# damp2_v0001.net
KiCad netlist of a schematic drawn in EAGLE
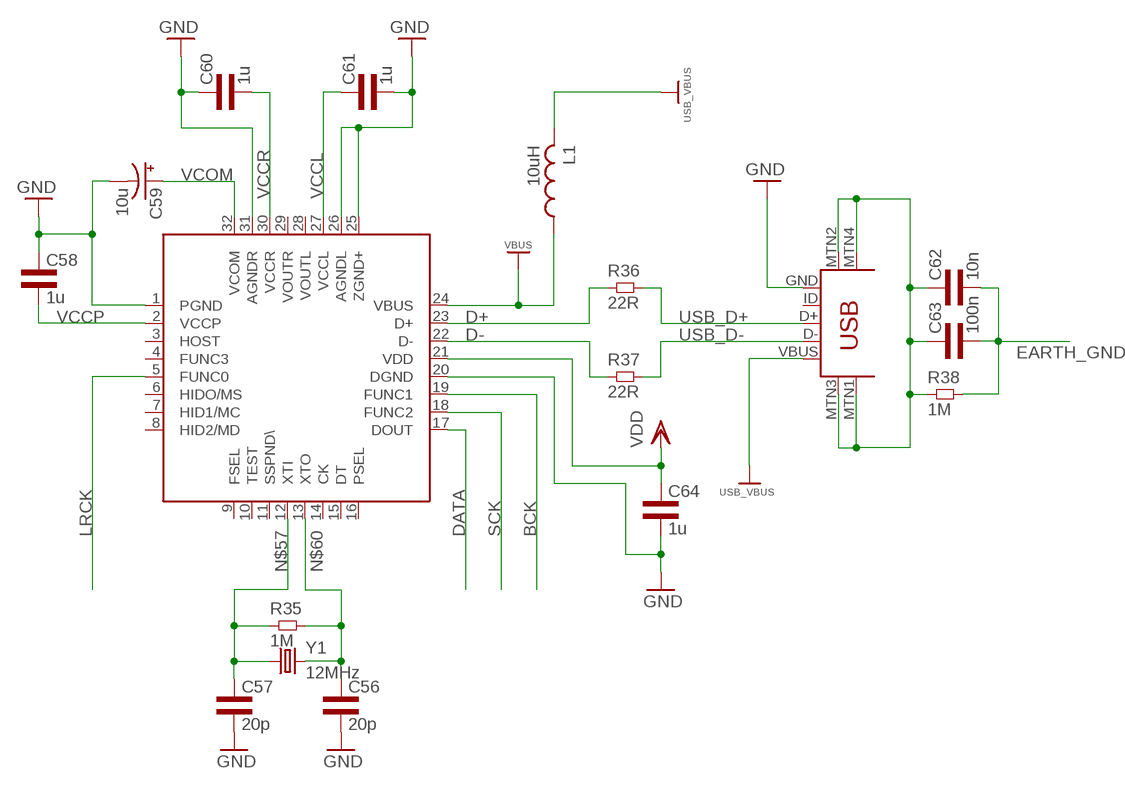
[diagram p0: schematic, sheet 1]
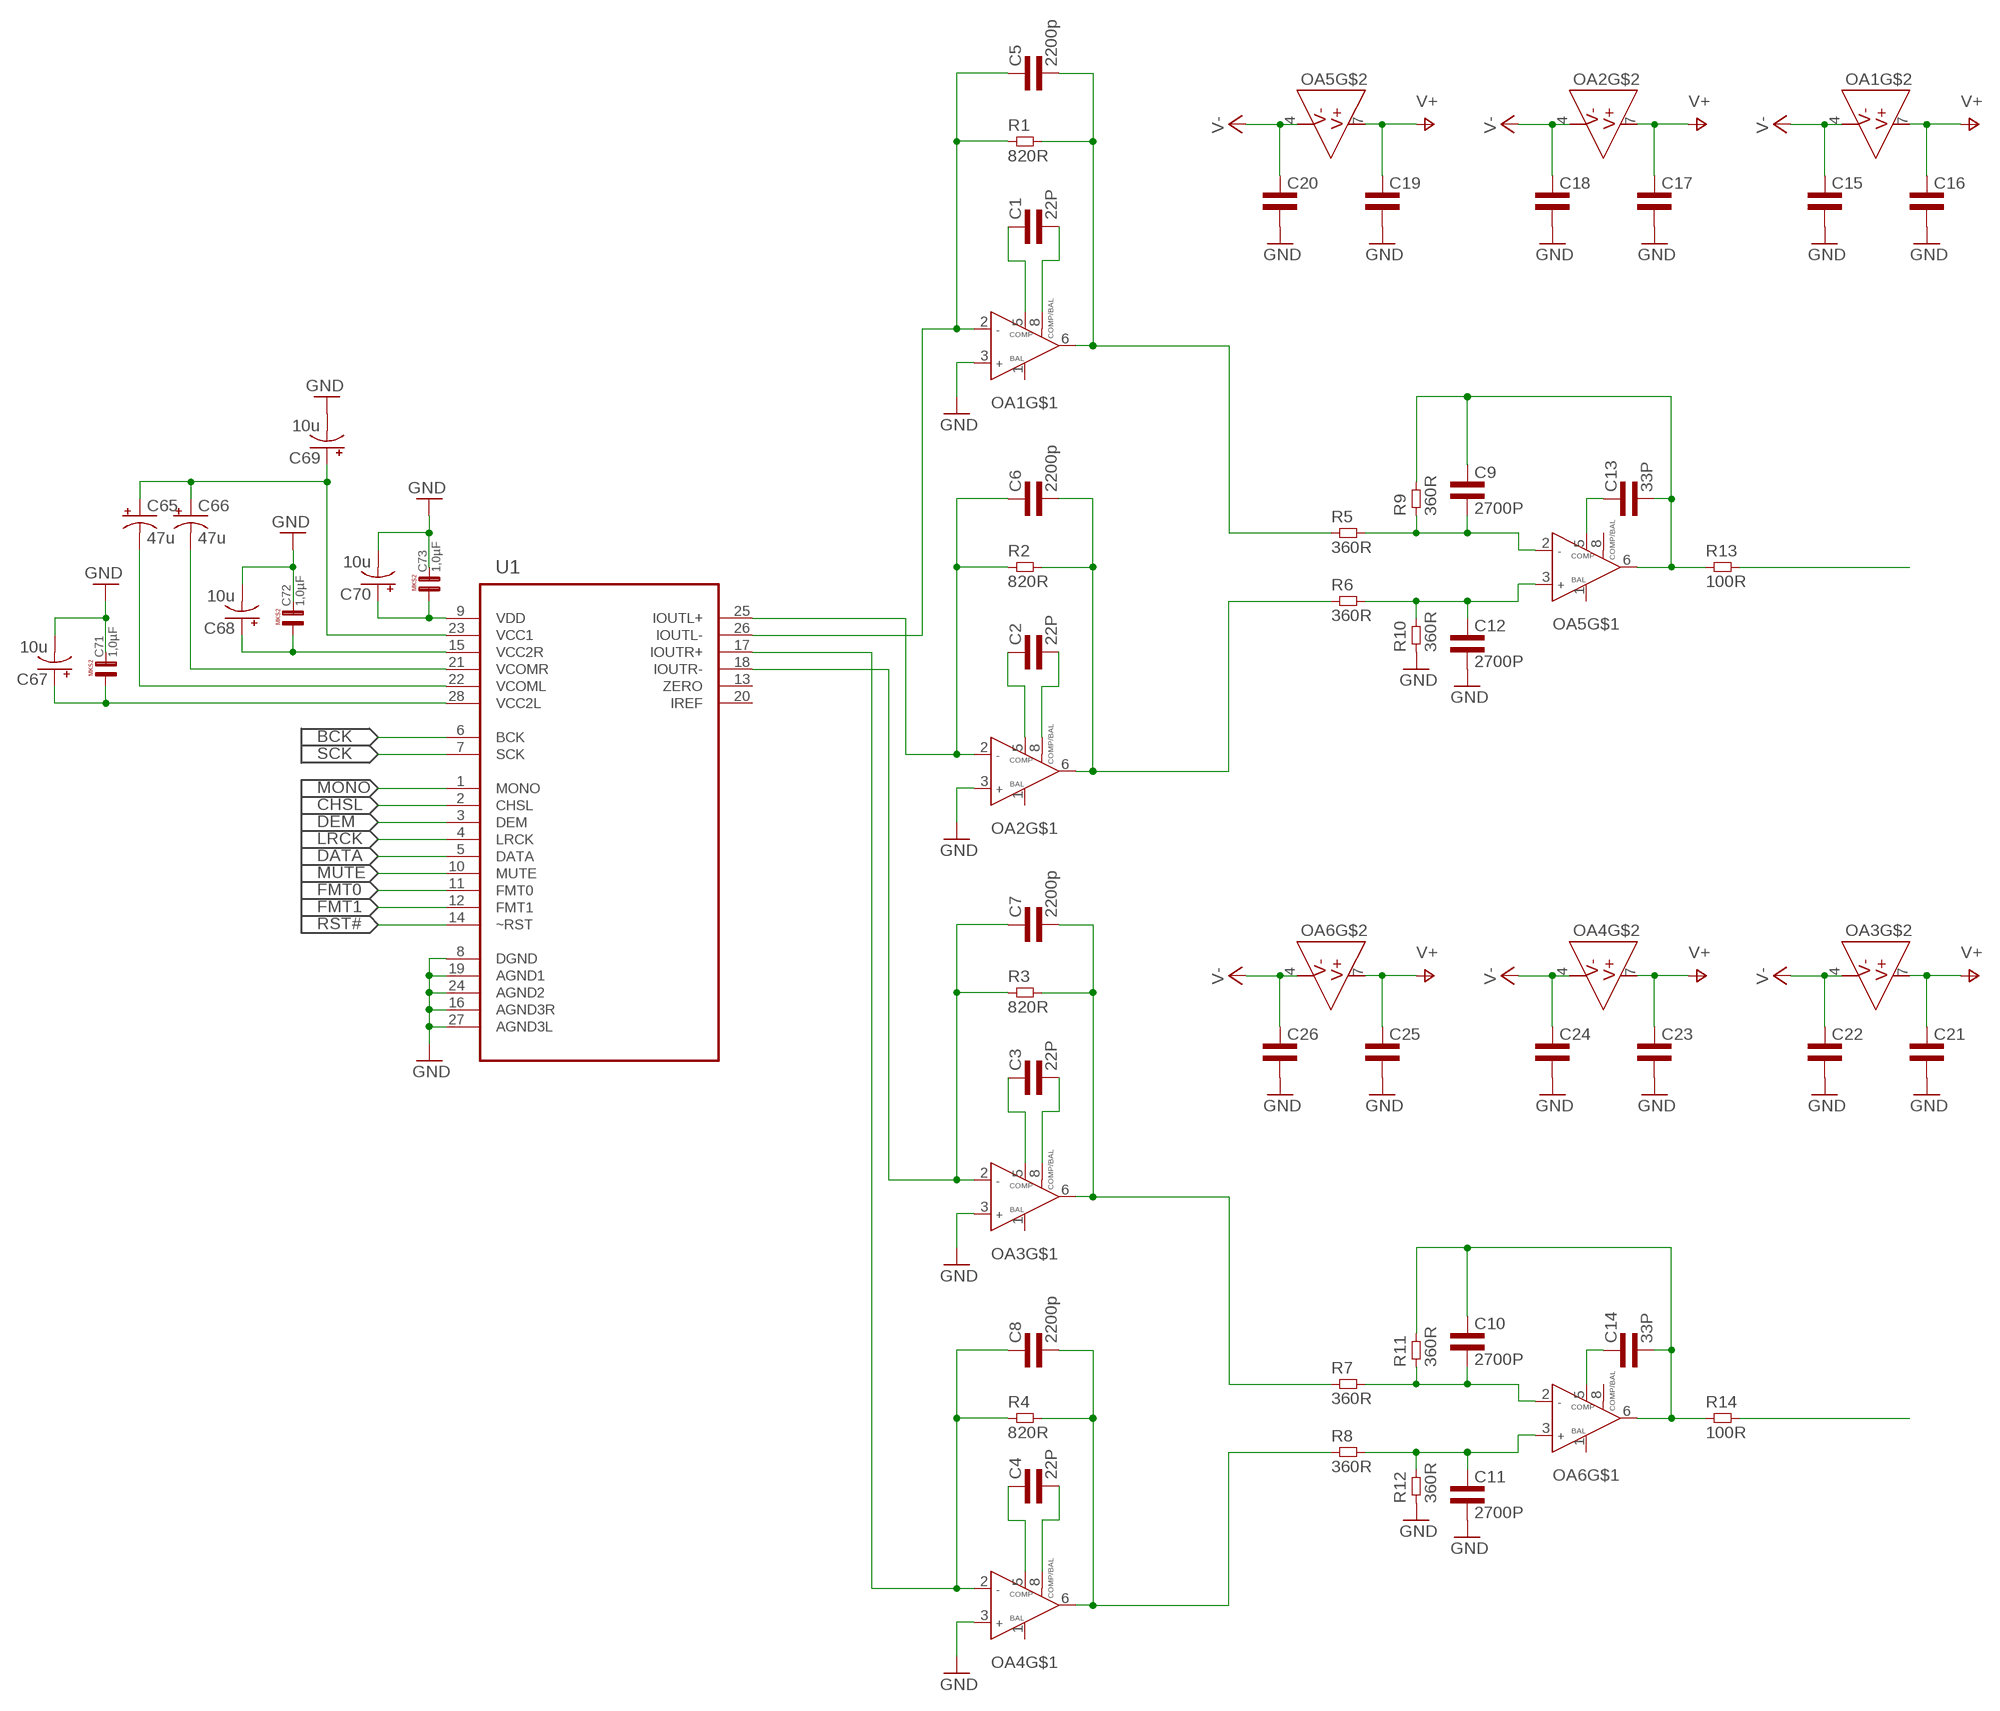
[diagram p1: schematic, sheet 2]
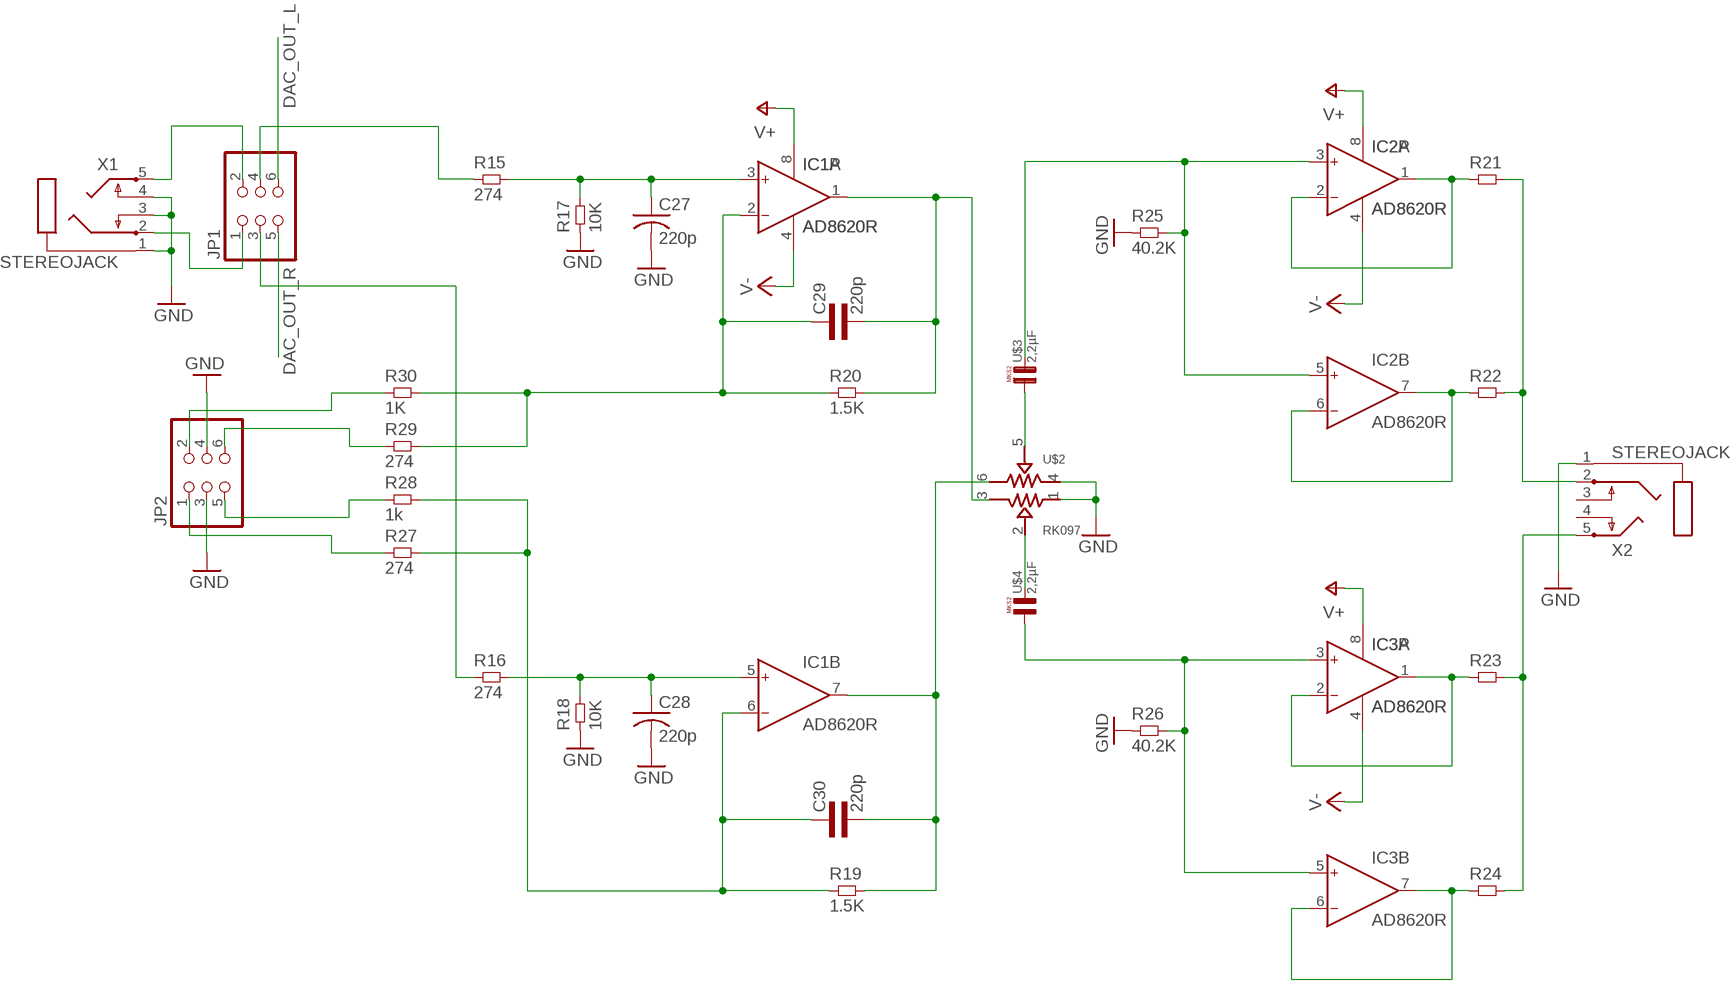
[diagram p2: schematic, sheet 3]

(export (version "E")
  (design (tool "Eeschema 10.0.6"))
  (components
    (comp (ref "C56")
      (value "20p")
      (footprint "eagle-import:0603L3")
      (libsource (lib "eagle-import") (part "CAP0603L3"))
    )
    (comp (ref "C57")
      (value "20p")
      (footprint "eagle-import:0603L3")
      (libsource (lib "eagle-import") (part "CAP0603L3"))
    )
    (comp (ref "C58")
      (value "1u")
      (footprint "eagle-import:0603L3")
      (libsource (lib "eagle-import") (part "CAP0603L3"))
    )
    (comp (ref "C59")
      (value "10u")
      (footprint "eagle-import:E1,8-4")
      (libsource (lib "eagle-import") (part "CPOL-USE1.8-4"))
    )
    (comp (ref "C60")
      (value "1u")
      (footprint "eagle-import:0603L3")
      (libsource (lib "eagle-import") (part "CAP0603L3"))
    )
    (comp (ref "C61")
      (value "1u")
      (footprint "eagle-import:0603L3")
      (libsource (lib "eagle-import") (part "CAP0603L3"))
    )
    (comp (ref "C62")
      (value "10n")
      (footprint "eagle-import:0603L3")
      (libsource (lib "eagle-import") (part "CAP0603L3"))
    )
    (comp (ref "C63")
      (value "100n")
      (footprint "eagle-import:0603L3")
      (libsource (lib "eagle-import") (part "CAP0603L3"))
    )
    (comp (ref "C64")
      (value "1u")
      (footprint "eagle-import:0603L3")
      (libsource (lib "eagle-import") (part "CAP0603L3"))
    )
    (comp (ref "L1")
      (value "10uH")
      (footprint "eagle-import:L3225M")
      (libsource (lib "eagle-import") (part "L-USL3225M"))
    )
    (comp (ref "R35")
      (value "1M")
      (footprint "eagle-import:0603L3")
      (libsource (lib "eagle-import") (part "RES0603L3"))
    )
    (comp (ref "R36")
      (value "22R")
      (footprint "eagle-import:0603L3")
      (libsource (lib "eagle-import") (part "RES0603L3"))
    )
    (comp (ref "R37")
      (value "22R")
      (footprint "eagle-import:0603L3")
      (libsource (lib "eagle-import") (part "RES0603L3"))
    )
    (comp (ref "R38")
      (value "1M")
      (footprint "eagle-import:0603L3")
      (libsource (lib "eagle-import") (part "RES0603L3"))
    )
    (comp (ref "U$1")
      (value "PCM2707_V1_PCM2704C_PCM2707")
      (footprint "eagle-import:PCM2707_V1_PCM2704C_PCM2707")
      (libsource (lib "eagle-import") (part "PCM2707_V1_PCM2704C_PCM2707"))
    )
    (comp (ref "U$9")
      (value "USB-MINIB-5PIN")
      (footprint "eagle-import:USB-MINIB")
      (libsource (lib "eagle-import") (part "USB-MINIB-5PIN"))
    )
    (comp (ref "Y1")
      (value "12MHz")
      (footprint "eagle-import:HC49US")
      (libsource (lib "eagle-import") (part "CRYSTALHC49US"))
    )
    (comp (ref "C1")
      (value "22P")
      (footprint "eagle-import:0603L3")
      (libsource (lib "eagle-import") (part "CAP0603L3"))
    )
    (comp (ref "C2")
      (value "22P")
      (footprint "eagle-import:0603L3")
      (libsource (lib "eagle-import") (part "CAP0603L3"))
    )
    (comp (ref "C3")
      (value "22P")
      (footprint "eagle-import:0603L3")
      (libsource (lib "eagle-import") (part "CAP0603L3"))
    )
    (comp (ref "C4")
      (value "22P")
      (footprint "eagle-import:0603L3")
      (libsource (lib "eagle-import") (part "CAP0603L3"))
    )
    (comp (ref "C5")
      (value "2200p")
      (footprint "eagle-import:0603L3")
      (libsource (lib "eagle-import") (part "CAP0603L3"))
    )
    (comp (ref "C6")
      (value "2200p")
      (footprint "eagle-import:0603L3")
      (libsource (lib "eagle-import") (part "CAP0603L3"))
    )
    (comp (ref "C7")
      (value "2200p")
      (footprint "eagle-import:0603L3")
      (libsource (lib "eagle-import") (part "CAP0603L3"))
    )
    (comp (ref "C8")
      (value "2200p")
      (footprint "eagle-import:0603L3")
      (libsource (lib "eagle-import") (part "CAP0603L3"))
    )
    (comp (ref "C9")
      (value "2700P")
      (footprint "eagle-import:0805L3")
      (libsource (lib "eagle-import") (part "CAP0805L3"))
    )
    (comp (ref "C10")
      (value "2700P")
      (footprint "eagle-import:0805L3")
      (libsource (lib "eagle-import") (part "CAP0805L3"))
    )
    (comp (ref "C11")
      (value "2700P")
      (footprint "eagle-import:0805L3")
      (libsource (lib "eagle-import") (part "CAP0805L3"))
    )
    (comp (ref "C12")
      (value "2700P")
      (footprint "eagle-import:0805L3")
      (libsource (lib "eagle-import") (part "CAP0805L3"))
    )
    (comp (ref "C13")
      (value "33P")
      (footprint "eagle-import:0603L3")
      (libsource (lib "eagle-import") (part "CAP0603L3"))
    )
    (comp (ref "C14")
      (value "33P")
      (footprint "eagle-import:0603L3")
      (libsource (lib "eagle-import") (part "CAP0603L3"))
    )
    (comp (ref "C15")
      (value "CAP0603L3")
      (footprint "eagle-import:0603L3")
      (libsource (lib "eagle-import") (part "CAP0603L3"))
    )
    (comp (ref "C16")
      (value "CAP0603L3")
      (footprint "eagle-import:0603L3")
      (libsource (lib "eagle-import") (part "CAP0603L3"))
    )
    (comp (ref "C17")
      (value "CAP0603L3")
      (footprint "eagle-import:0603L3")
      (libsource (lib "eagle-import") (part "CAP0603L3"))
    )
    (comp (ref "C18")
      (value "CAP0603L3")
      (footprint "eagle-import:0603L3")
      (libsource (lib "eagle-import") (part "CAP0603L3"))
    )
    (comp (ref "C19")
      (value "CAP0603L3")
      (footprint "eagle-import:0603L3")
      (libsource (lib "eagle-import") (part "CAP0603L3"))
    )
    (comp (ref "C20")
      (value "CAP0603L3")
      (footprint "eagle-import:0603L3")
      (libsource (lib "eagle-import") (part "CAP0603L3"))
    )
    (comp (ref "C21")
      (value "CAP0603L3")
      (footprint "eagle-import:0603L3")
      (libsource (lib "eagle-import") (part "CAP0603L3"))
    )
    (comp (ref "C22")
      (value "CAP0603L3")
      (footprint "eagle-import:0603L3")
      (libsource (lib "eagle-import") (part "CAP0603L3"))
    )
    (comp (ref "C23")
      (value "CAP0603L3")
      (footprint "eagle-import:0603L3")
      (libsource (lib "eagle-import") (part "CAP0603L3"))
    )
    (comp (ref "C24")
      (value "CAP0603L3")
      (footprint "eagle-import:0603L3")
      (libsource (lib "eagle-import") (part "CAP0603L3"))
    )
    (comp (ref "C25")
      (value "CAP0603L3")
      (footprint "eagle-import:0603L3")
      (libsource (lib "eagle-import") (part "CAP0603L3"))
    )
    (comp (ref "C26")
      (value "CAP0603L3")
      (footprint "eagle-import:0603L3")
      (libsource (lib "eagle-import") (part "CAP0603L3"))
    )
    (comp (ref "C65")
      (value "47u")
      (footprint "eagle-import:A_3216-18W")
      (libsource (lib "eagle-import") (part "CPOL-USA/3216-18W"))
    )
    (comp (ref "C66")
      (value "47u")
      (footprint "eagle-import:A_3216-18W")
      (libsource (lib "eagle-import") (part "CPOL-USA/3216-18W"))
    )
    (comp (ref "C67")
      (value "10u")
      (footprint "eagle-import:A_3216-18W")
      (libsource (lib "eagle-import") (part "CPOL-USA/3216-18W"))
    )
    (comp (ref "C68")
      (value "10u")
      (footprint "eagle-import:A_3216-18W")
      (libsource (lib "eagle-import") (part "CPOL-USA/3216-18W"))
    )
    (comp (ref "C69")
      (value "10u")
      (footprint "eagle-import:A_3216-18W")
      (libsource (lib "eagle-import") (part "CPOL-USA/3216-18W"))
    )
    (comp (ref "C70")
      (value "10u")
      (footprint "eagle-import:A_3216-18W")
      (libsource (lib "eagle-import") (part "CPOL-USA/3216-18W"))
    )
    (comp (ref "C71")
      (value "1,0µF")
      (footprint "eagle-import:R5B5")
      (libsource (lib "eagle-import") (part "1,0µF"))
    )
    (comp (ref "C72")
      (value "1,0µF")
      (footprint "eagle-import:R5B5")
      (libsource (lib "eagle-import") (part "1,0µF"))
    )
    (comp (ref "C73")
      (value "1,0µF")
      (footprint "eagle-import:R5B5")
      (libsource (lib "eagle-import") (part "1,0µF"))
    )
    (comp (ref "OA1")
      (value "NE5534DSOIC8")
      (footprint "eagle-import:SOIC-8")
      (libsource (lib "eagle-import") (part "NE5534SOIC8D"))
    )
    (comp (ref "OA2")
      (value "NE5534DSOIC8")
      (footprint "eagle-import:SOIC-8")
      (libsource (lib "eagle-import") (part "NE5534SOIC8D"))
    )
    (comp (ref "OA3")
      (value "NE5534DSOIC8")
      (footprint "eagle-import:SOIC-8")
      (libsource (lib "eagle-import") (part "NE5534SOIC8D"))
    )
    (comp (ref "OA4")
      (value "NE5534DSOIC8")
      (footprint "eagle-import:SOIC-8")
      (libsource (lib "eagle-import") (part "NE5534SOIC8D"))
    )
    (comp (ref "OA5")
      (value "NE5534ADSOIC8")
      (footprint "eagle-import:SOIC-8")
      (libsource (lib "eagle-import") (part "NE5534SOIC8AD"))
    )
    (comp (ref "OA6")
      (value "NE5534ADSOIC8")
      (footprint "eagle-import:SOIC-8")
      (libsource (lib "eagle-import") (part "NE5534SOIC8AD"))
    )
    (comp (ref "R1")
      (value "820R")
      (footprint "eagle-import:0603L3")
      (libsource (lib "eagle-import") (part "RES0603L3"))
    )
    (comp (ref "R2")
      (value "820R")
      (footprint "eagle-import:0603L3")
      (libsource (lib "eagle-import") (part "RES0603L3"))
    )
    (comp (ref "R3")
      (value "820R")
      (footprint "eagle-import:0603L3")
      (libsource (lib "eagle-import") (part "RES0603L3"))
    )
    (comp (ref "R4")
      (value "820R")
      (footprint "eagle-import:0603L3")
      (libsource (lib "eagle-import") (part "RES0603L3"))
    )
    (comp (ref "R5")
      (value "360R")
      (footprint "eagle-import:0805L3")
      (libsource (lib "eagle-import") (part "RES0805L3"))
    )
    (comp (ref "R6")
      (value "360R")
      (footprint "eagle-import:0805L3")
      (libsource (lib "eagle-import") (part "RES0805L3"))
    )
    (comp (ref "R7")
      (value "360R")
      (footprint "eagle-import:0805L3")
      (libsource (lib "eagle-import") (part "RES0805L3"))
    )
    (comp (ref "R8")
      (value "360R")
      (footprint "eagle-import:0805L3")
      (libsource (lib "eagle-import") (part "RES0805L3"))
    )
    (comp (ref "R9")
      (value "360R")
      (footprint "eagle-import:0805L3")
      (libsource (lib "eagle-import") (part "RES0805L3"))
    )
    (comp (ref "R10")
      (value "360R")
      (footprint "eagle-import:0805L3")
      (libsource (lib "eagle-import") (part "RES0805L3"))
    )
    (comp (ref "R11")
      (value "360R")
      (footprint "eagle-import:0805L3")
      (libsource (lib "eagle-import") (part "RES0805L3"))
    )
    (comp (ref "R12")
      (value "360R")
      (footprint "eagle-import:0805L3")
      (libsource (lib "eagle-import") (part "RES0805L3"))
    )
    (comp (ref "R13")
      (value "100R")
      (footprint "eagle-import:0805L3")
      (libsource (lib "eagle-import") (part "RES0805L3"))
    )
    (comp (ref "R14")
      (value "100R")
      (footprint "eagle-import:0805L3")
      (libsource (lib "eagle-import") (part "RES0805L3"))
    )
    (comp (ref "U1")
      (value "TEXAS-INSTRUMENTS_BY_ELEMENT14_BATCH_1_PCM1794ADB")
      (footprint "eagle-import:TEXAS-INSTRUMENTS_BY_ELEMENT14_BATCH_1_SOP65P780X200-28N")
      (fields (field (name "MPN") "PCM1794ADB"))
      (libsource (lib "eagle-import") (part "TEXAS-INSTRUMENTS_BY_ELEMENT14_BATCH_1_PCM1794ADB"))
    )
    (comp (ref "C27")
      (value "220p")
      (footprint "eagle-import:C025-025X050")
      (libsource (lib "eagle-import") (part "C-US025-025X050"))
    )
    (comp (ref "C28")
      (value "220p")
      (footprint "eagle-import:C025-025X050")
      (libsource (lib "eagle-import") (part "C-US025-025X050"))
    )
    (comp (ref "C29")
      (value "220p")
      (footprint "eagle-import:0805L3")
      (libsource (lib "eagle-import") (part "CAP0805L3"))
    )
    (comp (ref "C30")
      (value "220p")
      (footprint "eagle-import:0805L3")
      (libsource (lib "eagle-import") (part "CAP0805L3"))
    )
    (comp (ref "IC1")
      (value "AD8620R")
      (footprint "eagle-import:SO8")
      (fields (field (name "MF") "ALTERA CORPORATION") (field (name "MPN") "AD8620ARZ"))
      (libsource (lib "eagle-import") (part "AD8620R"))
    )
    (comp (ref "IC2")
      (value "AD8620R")
      (footprint "eagle-import:SO8")
      (fields (field (name "MF") "ALTERA CORPORATION") (field (name "MPN") "AD8620ARZ"))
      (libsource (lib "eagle-import") (part "AD8620R"))
    )
    (comp (ref "IC3")
      (value "AD8620R")
      (footprint "eagle-import:SO8")
      (fields (field (name "MF") "ALTERA CORPORATION") (field (name "MPN") "AD8620ARZ"))
      (libsource (lib "eagle-import") (part "AD8620R"))
    )
    (comp (ref "JP1")
      (value "PINHD-2X3")
      (footprint "eagle-import:2X03")
      (libsource (lib "eagle-import") (part "PINHD-2X3"))
    )
    (comp (ref "JP2")
      (value "PINHD-2X3")
      (footprint "eagle-import:2X03")
      (libsource (lib "eagle-import") (part "PINHD-2X3"))
    )
    (comp (ref "R15")
      (value "274")
      (footprint "eagle-import:0805L3")
      (libsource (lib "eagle-import") (part "RES0805L3"))
    )
    (comp (ref "R16")
      (value "274")
      (footprint "eagle-import:0805L3")
      (libsource (lib "eagle-import") (part "RES0805L3"))
    )
    (comp (ref "R17")
      (value "10K")
      (footprint "eagle-import:0805L3")
      (libsource (lib "eagle-import") (part "RES0805L3"))
    )
    (comp (ref "R18")
      (value "10K")
      (footprint "eagle-import:0805L3")
      (libsource (lib "eagle-import") (part "RES0805L3"))
    )
    (comp (ref "R19")
      (value "1.5K")
      (footprint "eagle-import:0805L3")
      (libsource (lib "eagle-import") (part "RES0805L3"))
    )
    (comp (ref "R20")
      (value "1.5K")
      (footprint "eagle-import:0805L3")
      (libsource (lib "eagle-import") (part "RES0805L3"))
    )
    (comp (ref "R21")
      (value "RES1206L3")
      (footprint "eagle-import:1206L3")
      (libsource (lib "eagle-import") (part "RES1206L3"))
    )
    (comp (ref "R22")
      (value "RES1206L3")
      (footprint "eagle-import:1206L3")
      (libsource (lib "eagle-import") (part "RES1206L3"))
    )
    (comp (ref "R23")
      (value "RES1206L3")
      (footprint "eagle-import:1206L3")
      (libsource (lib "eagle-import") (part "RES1206L3"))
    )
    (comp (ref "R24")
      (value "RES1206L3")
      (footprint "eagle-import:1206L3")
      (libsource (lib "eagle-import") (part "RES1206L3"))
    )
    (comp (ref "R25")
      (value "40.2K")
      (footprint "eagle-import:0805L3")
      (libsource (lib "eagle-import") (part "RES0805L3"))
    )
    (comp (ref "R26")
      (value "40.2K")
      (footprint "eagle-import:0805L3")
      (libsource (lib "eagle-import") (part "RES0805L3"))
    )
    (comp (ref "R27")
      (value "274")
      (footprint "eagle-import:0805L3")
      (libsource (lib "eagle-import") (part "RES0805L3"))
    )
    (comp (ref "R28")
      (value "1k")
      (footprint "eagle-import:0805L3")
      (libsource (lib "eagle-import") (part "RES0805L3"))
    )
    (comp (ref "R29")
      (value "274")
      (footprint "eagle-import:0805L3")
      (libsource (lib "eagle-import") (part "RES0805L3"))
    )
    (comp (ref "R30")
      (value "1K")
      (footprint "eagle-import:0805L3")
      (libsource (lib "eagle-import") (part "RES0805L3"))
    )
    (comp (ref "U$2")
      (value "RK097")
      (footprint "eagle-import:RK097")
      (libsource (lib "eagle-import") (part "RK097"))
    )
    (comp (ref "U$3")
      (value "2,2µF")
      (footprint "eagle-import:R5B7K2")
      (libsource (lib "eagle-import") (part "2,2µF"))
    )
    (comp (ref "U$4")
      (value "2,2µF")
      (footprint "eagle-import:R5B7K2")
      (libsource (lib "eagle-import") (part "2,2µF"))
    )
    (comp (ref "X1")
      (value "STEREOJACK")
      (footprint "eagle-import:STX3100")
      (libsource (lib "eagle-import") (part "STEREOJACK"))
    )
    (comp (ref "X2")
      (value "STEREOJACK")
      (footprint "eagle-import:STX3100")
      (libsource (lib "eagle-import") (part "STEREOJACK"))
    )
  )
  (nets
    (net (code "1") (name "BCK") (class "Default")
      (node (ref "U$1") (pin "19") (pinfunction "FUNC1_19") (pintype "bidirectional"))
      (node (ref "U1") (pin "6") (pinfunction "BCK_6") (pintype "input"))
    )
    (net (code "2") (name "CHSL") (class "Default")
      (node (ref "U1") (pin "2") (pinfunction "CHSL_2") (pintype "input"))
    )
    (net (code "3") (name "D+") (class "Default")
      (node (ref "R36") (pin "P$1") (pinfunction "1_P$1") (pintype "bidirectional"))
      (node (ref "U$1") (pin "23") (pinfunction "D+_23") (pintype "bidirectional"))
    )
    (net (code "4") (name "D-") (class "Default")
      (node (ref "R37") (pin "P$1") (pinfunction "1_P$1") (pintype "bidirectional"))
      (node (ref "U$1") (pin "22") (pinfunction "D-_22") (pintype "bidirectional"))
    )
    (net (code "5") (name "DAC_OUT_L") (class "Default")
      (node (ref "JP1") (pin "6") (pinfunction "6_6") (pintype "passive"))
    )
    (net (code "6") (name "DAC_OUT_R") (class "Default")
      (node (ref "JP1") (pin "5") (pinfunction "5_5") (pintype "passive"))
    )
    (net (code "7") (name "DATA") (class "Default")
      (node (ref "U$1") (pin "17") (pinfunction "DOUT_17") (pintype "bidirectional"))
      (node (ref "U1") (pin "5") (pinfunction "DATA_5") (pintype "input"))
    )
    (net (code "8") (name "DEM") (class "Default")
      (node (ref "U1") (pin "3") (pinfunction "DEM_3") (pintype "input"))
    )
    (net (code "9") (name "EARTH_GND") (class "Default")
      (node (ref "C62") (pin "P$2") (pinfunction "2_P$2") (pintype "bidirectional"))
      (node (ref "C63") (pin "P$2") (pinfunction "2_P$2") (pintype "bidirectional"))
      (node (ref "R38") (pin "P$2") (pinfunction "2_P$2") (pintype "bidirectional"))
    )
    (net (code "10") (name "FMT0") (class "Default")
      (node (ref "U1") (pin "11") (pinfunction "FMT0_11") (pintype "input"))
    )
    (net (code "11") (name "FMT1") (class "Default")
      (node (ref "U1") (pin "12") (pinfunction "FMT1_12") (pintype "input"))
    )
    (net (code "12") (name "GND") (class "Default")
      (node (ref "C11") (pin "2") (pinfunction "2_2") (pintype "bidirectional"))
      (node (ref "C12") (pin "2") (pinfunction "2_2") (pintype "bidirectional"))
      (node (ref "C15") (pin "P$2") (pinfunction "2_P$2") (pintype "bidirectional"))
      (node (ref "C16") (pin "P$2") (pinfunction "2_P$2") (pintype "bidirectional"))
      (node (ref "C17") (pin "P$2") (pinfunction "2_P$2") (pintype "bidirectional"))
      (node (ref "C18") (pin "P$2") (pinfunction "2_P$2") (pintype "bidirectional"))
      (node (ref "C19") (pin "P$2") (pinfunction "2_P$2") (pintype "bidirectional"))
      (node (ref "C20") (pin "P$2") (pinfunction "2_P$2") (pintype "bidirectional"))
      (node (ref "C21") (pin "P$2") (pinfunction "2_P$2") (pintype "bidirectional"))
      (node (ref "C22") (pin "P$2") (pinfunction "2_P$2") (pintype "bidirectional"))
      (node (ref "C23") (pin "P$2") (pinfunction "2_P$2") (pintype "bidirectional"))
      (node (ref "C24") (pin "P$2") (pinfunction "2_P$2") (pintype "bidirectional"))
      (node (ref "C25") (pin "P$2") (pinfunction "2_P$2") (pintype "bidirectional"))
      (node (ref "C26") (pin "P$2") (pinfunction "2_P$2") (pintype "bidirectional"))
      (node (ref "C27") (pin "2") (pinfunction "2_2") (pintype "passive"))
      (node (ref "C28") (pin "2") (pinfunction "2_2") (pintype "passive"))
      (node (ref "C56") (pin "P$2") (pinfunction "2_P$2") (pintype "bidirectional"))
      (node (ref "C57") (pin "P$2") (pinfunction "2_P$2") (pintype "bidirectional"))
      (node (ref "C58") (pin "P$1") (pinfunction "1_P$1") (pintype "bidirectional"))
      (node (ref "C59") (pin "-") (pinfunction "-_-") (pintype "passive"))
      (node (ref "C60") (pin "P$1") (pinfunction "1_P$1") (pintype "bidirectional"))
      (node (ref "C61") (pin "P$2") (pinfunction "2_P$2") (pintype "bidirectional"))
      (node (ref "C64") (pin "P$2") (pinfunction "2_P$2") (pintype "bidirectional"))
      (node (ref "C67") (pin "-") (pinfunction "-_-") (pintype "passive"))
      (node (ref "C68") (pin "-") (pinfunction "-_-") (pintype "passive"))
      (node (ref "C69") (pin "-") (pinfunction "-_-") (pintype "passive"))
      (node (ref "C70") (pin "-") (pinfunction "-_-") (pintype "passive"))
      (node (ref "C71") (pin "2") (pinfunction "2_2") (pintype "passive"))
      (node (ref "C72") (pin "2") (pinfunction "2_2") (pintype "passive"))
      (node (ref "C73") (pin "2") (pinfunction "2_2") (pintype "passive"))
      (node (ref "JP2") (pin "3") (pinfunction "3_3") (pintype "passive"))
      (node (ref "JP2") (pin "4") (pinfunction "4_4") (pintype "passive"))
      (node (ref "OA1") (pin "3") (pinfunction "IN+_3") (pintype "bidirectional"))
      (node (ref "OA2") (pin "3") (pinfunction "IN+_3") (pintype "bidirectional"))
      (node (ref "OA3") (pin "3") (pinfunction "IN+_3") (pintype "bidirectional"))
      (node (ref "OA4") (pin "3") (pinfunction "IN+_3") (pintype "bidirectional"))
      (node (ref "R10") (pin "1") (pinfunction "1_1") (pintype "bidirectional"))
      (node (ref "R12") (pin "1") (pinfunction "1_1") (pintype "bidirectional"))
      (node (ref "R17") (pin "1") (pinfunction "1_1") (pintype "bidirectional"))
      (node (ref "R18") (pin "1") (pinfunction "1_1") (pintype "bidirectional"))
      (node (ref "R25") (pin "1") (pinfunction "1_1") (pintype "bidirectional"))
      (node (ref "R26") (pin "1") (pinfunction "1_1") (pintype "bidirectional"))
      (node (ref "U$1") (pin "1") (pinfunction "PGND_1") (pintype "bidirectional"))
      (node (ref "U$1") (pin "20") (pinfunction "DGND_20") (pintype "bidirectional"))
      (node (ref "U$1") (pin "25") (pinfunction "ZGND+_25") (pintype "bidirectional"))
      (node (ref "U$1") (pin "26") (pinfunction "AGNDL_26") (pintype "bidirectional"))
      (node (ref "U$1") (pin "31") (pinfunction "AGNDR_31") (pintype "bidirectional"))
      (node (ref "U$2") (pin "1") (pinfunction "1_1") (pintype "bidirectional"))
      (node (ref "U$2") (pin "4") (pinfunction "4_4") (pintype "bidirectional"))
      (node (ref "U$9") (pin "GND") (pinfunction "GND_GND") (pintype "bidirectional"))
      (node (ref "U1") (pin "16") (pinfunction "AGND3R_16") (pintype "passive"))
      (node (ref "U1") (pin "19") (pinfunction "AGND1_19") (pintype "passive"))
      (node (ref "U1") (pin "24") (pinfunction "AGND2_24") (pintype "passive"))
      (node (ref "U1") (pin "27") (pinfunction "AGND3L_27") (pintype "passive"))
      (node (ref "U1") (pin "8") (pinfunction "DGND_8") (pintype "passive"))
      (node (ref "X1") (pin "1") (pinfunction "1_1") (pintype "passive"))
      (node (ref "X1") (pin "3") (pinfunction "3_3") (pintype "passive"))
      (node (ref "X1") (pin "4") (pinfunction "4_4") (pintype "passive"))
      (node (ref "X2") (pin "1") (pinfunction "1_1") (pintype "passive"))
    )
    (net (code "13") (name "LRCK") (class "Default")
      (node (ref "U$1") (pin "5") (pinfunction "FUNC0_5") (pintype "bidirectional"))
      (node (ref "U1") (pin "4") (pinfunction "LRCK_4") (pintype "input"))
    )
    (net (code "14") (name "MONO") (class "Default")
      (node (ref "U1") (pin "1") (pinfunction "MONO_1") (pintype "input"))
    )
    (net (code "15") (name "MUTE") (class "Default")
      (node (ref "U1") (pin "10") (pinfunction "MUTE_10") (pintype "input"))
    )
    (net (code "16") (name "N$57") (class "Default")
      (node (ref "C57") (pin "P$1") (pinfunction "1_P$1") (pintype "bidirectional"))
      (node (ref "R35") (pin "P$1") (pinfunction "1_P$1") (pintype "bidirectional"))
      (node (ref "U$1") (pin "12") (pinfunction "XTI_12") (pintype "bidirectional"))
      (node (ref "Y1") (pin "1") (pinfunction "1_1") (pintype "passive"))
    )
    (net (code "17") (name "N$60") (class "Default")
      (node (ref "C56") (pin "P$1") (pinfunction "1_P$1") (pintype "bidirectional"))
      (node (ref "R35") (pin "P$2") (pinfunction "2_P$2") (pintype "bidirectional"))
      (node (ref "U$1") (pin "13") (pinfunction "XTO_13") (pintype "bidirectional"))
      (node (ref "Y1") (pin "2") (pinfunction "2_2") (pintype "passive"))
    )
    (net (code "18") (name "Net-(C1-1)") (class "Default")
      (node (ref "C1") (pin "P$1") (pinfunction "1_P$1") (pintype "bidirectional"))
      (node (ref "OA1") (pin "5") (pinfunction "COMP_5") (pintype "bidirectional"))
    )
    (net (code "19") (name "Net-(C1-2)") (class "Default")
      (node (ref "C1") (pin "P$2") (pinfunction "2_P$2") (pintype "bidirectional"))
      (node (ref "OA1") (pin "8") (pinfunction "COMP/BAL_8") (pintype "bidirectional"))
    )
    (net (code "20") (name "Net-(C2-1)") (class "Default")
      (node (ref "C2") (pin "P$1") (pinfunction "1_P$1") (pintype "bidirectional"))
      (node (ref "OA2") (pin "5") (pinfunction "COMP_5") (pintype "bidirectional"))
    )
    (net (code "21") (name "Net-(C2-2)") (class "Default")
      (node (ref "C2") (pin "P$2") (pinfunction "2_P$2") (pintype "bidirectional"))
      (node (ref "OA2") (pin "8") (pinfunction "COMP/BAL_8") (pintype "bidirectional"))
    )
    (net (code "22") (name "Net-(C3-1)") (class "Default")
      (node (ref "C3") (pin "P$1") (pinfunction "1_P$1") (pintype "bidirectional"))
      (node (ref "OA3") (pin "5") (pinfunction "COMP_5") (pintype "bidirectional"))
    )
    (net (code "23") (name "Net-(C3-2)") (class "Default")
      (node (ref "C3") (pin "P$2") (pinfunction "2_P$2") (pintype "bidirectional"))
      (node (ref "OA3") (pin "8") (pinfunction "COMP/BAL_8") (pintype "bidirectional"))
    )
    (net (code "24") (name "Net-(C4-1)") (class "Default")
      (node (ref "C4") (pin "P$1") (pinfunction "1_P$1") (pintype "bidirectional"))
      (node (ref "OA4") (pin "5") (pinfunction "COMP_5") (pintype "bidirectional"))
    )
    (net (code "25") (name "Net-(C4-2)") (class "Default")
      (node (ref "C4") (pin "P$2") (pinfunction "2_P$2") (pintype "bidirectional"))
      (node (ref "OA4") (pin "8") (pinfunction "COMP/BAL_8") (pintype "bidirectional"))
    )
    (net (code "26") (name "Net-(C5-1)") (class "Default")
      (node (ref "C5") (pin "P$1") (pinfunction "1_P$1") (pintype "bidirectional"))
      (node (ref "OA1") (pin "2") (pinfunction "IN-_2") (pintype "bidirectional"))
      (node (ref "R1") (pin "P$1") (pinfunction "1_P$1") (pintype "bidirectional"))
      (node (ref "U1") (pin "26") (pinfunction "IOUTL-_26") (pintype "output"))
    )
    (net (code "27") (name "Net-(C5-2)") (class "Default")
      (node (ref "C5") (pin "P$2") (pinfunction "2_P$2") (pintype "bidirectional"))
      (node (ref "OA1") (pin "6") (pinfunction "OUT_6") (pintype "bidirectional"))
      (node (ref "R1") (pin "P$2") (pinfunction "2_P$2") (pintype "bidirectional"))
      (node (ref "R5") (pin "1") (pinfunction "1_1") (pintype "bidirectional"))
    )
    (net (code "28") (name "Net-(C6-1)") (class "Default")
      (node (ref "C6") (pin "P$1") (pinfunction "1_P$1") (pintype "bidirectional"))
      (node (ref "OA2") (pin "2") (pinfunction "IN-_2") (pintype "bidirectional"))
      (node (ref "R2") (pin "P$1") (pinfunction "1_P$1") (pintype "bidirectional"))
      (node (ref "U1") (pin "25") (pinfunction "IOUTL+_25") (pintype "output"))
    )
    (net (code "29") (name "Net-(C6-2)") (class "Default")
      (node (ref "C6") (pin "P$2") (pinfunction "2_P$2") (pintype "bidirectional"))
      (node (ref "OA2") (pin "6") (pinfunction "OUT_6") (pintype "bidirectional"))
      (node (ref "R2") (pin "P$2") (pinfunction "2_P$2") (pintype "bidirectional"))
      (node (ref "R6") (pin "1") (pinfunction "1_1") (pintype "bidirectional"))
    )
    (net (code "30") (name "Net-(C7-1)") (class "Default")
      (node (ref "C7") (pin "P$1") (pinfunction "1_P$1") (pintype "bidirectional"))
      (node (ref "OA3") (pin "2") (pinfunction "IN-_2") (pintype "bidirectional"))
      (node (ref "R3") (pin "P$1") (pinfunction "1_P$1") (pintype "bidirectional"))
      (node (ref "U1") (pin "18") (pinfunction "IOUTR-_18") (pintype "output"))
    )
    (net (code "31") (name "Net-(C7-2)") (class "Default")
      (node (ref "C7") (pin "P$2") (pinfunction "2_P$2") (pintype "bidirectional"))
      (node (ref "OA3") (pin "6") (pinfunction "OUT_6") (pintype "bidirectional"))
      (node (ref "R3") (pin "P$2") (pinfunction "2_P$2") (pintype "bidirectional"))
      (node (ref "R7") (pin "1") (pinfunction "1_1") (pintype "bidirectional"))
    )
    (net (code "32") (name "Net-(C8-1)") (class "Default")
      (node (ref "C8") (pin "P$1") (pinfunction "1_P$1") (pintype "bidirectional"))
      (node (ref "OA4") (pin "2") (pinfunction "IN-_2") (pintype "bidirectional"))
      (node (ref "R4") (pin "P$1") (pinfunction "1_P$1") (pintype "bidirectional"))
      (node (ref "U1") (pin "17") (pinfunction "IOUTR+_17") (pintype "output"))
    )
    (net (code "33") (name "Net-(C8-2)") (class "Default")
      (node (ref "C8") (pin "P$2") (pinfunction "2_P$2") (pintype "bidirectional"))
      (node (ref "OA4") (pin "6") (pinfunction "OUT_6") (pintype "bidirectional"))
      (node (ref "R4") (pin "P$2") (pinfunction "2_P$2") (pintype "bidirectional"))
      (node (ref "R8") (pin "1") (pinfunction "1_1") (pintype "bidirectional"))
    )
    (net (code "34") (name "Net-(C13-1)") (class "Default")
      (node (ref "C13") (pin "P$1") (pinfunction "1_P$1") (pintype "bidirectional"))
      (node (ref "OA5") (pin "5") (pinfunction "COMP_5") (pintype "bidirectional"))
    )
    (net (code "35") (name "Net-(C13-2)") (class "Default")
      (node (ref "C13") (pin "P$2") (pinfunction "2_P$2") (pintype "bidirectional"))
      (node (ref "C9") (pin "1") (pinfunction "1_1") (pintype "bidirectional"))
      (node (ref "OA5") (pin "6") (pinfunction "OUT_6") (pintype "bidirectional"))
      (node (ref "R13") (pin "1") (pinfunction "1_1") (pintype "bidirectional"))
      (node (ref "R9") (pin "2") (pinfunction "2_2") (pintype "bidirectional"))
    )
    (net (code "36") (name "Net-(C14-1)") (class "Default")
      (node (ref "C14") (pin "P$1") (pinfunction "1_P$1") (pintype "bidirectional"))
      (node (ref "OA6") (pin "5") (pinfunction "COMP_5") (pintype "bidirectional"))
    )
    (net (code "37") (name "Net-(C14-2)") (class "Default")
      (node (ref "C10") (pin "1") (pinfunction "1_1") (pintype "bidirectional"))
      (node (ref "C14") (pin "P$2") (pinfunction "2_P$2") (pintype "bidirectional"))
      (node (ref "OA6") (pin "6") (pinfunction "OUT_6") (pintype "bidirectional"))
      (node (ref "R11") (pin "2") (pinfunction "2_2") (pintype "bidirectional"))
      (node (ref "R14") (pin "1") (pinfunction "1_1") (pintype "bidirectional"))
    )
    (net (code "38") (name "Net-(C62-1)") (class "Default")
      (node (ref "C62") (pin "P$1") (pinfunction "1_P$1") (pintype "bidirectional"))
      (node (ref "C63") (pin "P$1") (pinfunction "1_P$1") (pintype "bidirectional"))
      (node (ref "R38") (pin "P$1") (pinfunction "1_P$1") (pintype "bidirectional"))
      (node (ref "U$9") (pin "MTN1") (pinfunction "MTN2_MTN1") (pintype "bidirectional"))
      (node (ref "U$9") (pin "MTN2") (pinfunction "MTN3_MTN2") (pintype "bidirectional"))
      (node (ref "U$9") (pin "MTN3") (pinfunction "MTN1_MTN3") (pintype "bidirectional"))
      (node (ref "U$9") (pin "MTN4") (pinfunction "MTN4_MTN4") (pintype "bidirectional"))
    )
    (net (code "39") (name "Net-(IC1A-IN+)") (class "Default")
      (node (ref "C27") (pin "1") (pinfunction "1_1") (pintype "passive"))
      (node (ref "IC1") (pin "3") (pinfunction "IN+_3") (pintype "input"))
      (node (ref "R15") (pin "2") (pinfunction "2_2") (pintype "bidirectional"))
      (node (ref "R17") (pin "2") (pinfunction "2_2") (pintype "bidirectional"))
    )
    (net (code "40") (name "Net-(IC1A-IN-)") (class "Default")
      (node (ref "C29") (pin "1") (pinfunction "1_1") (pintype "bidirectional"))
      (node (ref "IC1") (pin "2") (pinfunction "IN-_2") (pintype "input"))
      (node (ref "R20") (pin "1") (pinfunction "1_1") (pintype "bidirectional"))
      (node (ref "R29") (pin "2") (pinfunction "2_2") (pintype "bidirectional"))
      (node (ref "R30") (pin "2") (pinfunction "2_2") (pintype "bidirectional"))
    )
    (net (code "41") (name "Net-(IC1A-OUT)") (class "Default")
      (node (ref "C29") (pin "2") (pinfunction "2_2") (pintype "bidirectional"))
      (node (ref "IC1") (pin "1") (pinfunction "OUT_1") (pintype "output"))
      (node (ref "R20") (pin "2") (pinfunction "2_2") (pintype "bidirectional"))
      (node (ref "U$2") (pin "3") (pinfunction "3_3") (pintype "bidirectional"))
    )
    (net (code "42") (name "Net-(IC1B-IN+)") (class "Default")
      (node (ref "C28") (pin "1") (pinfunction "1_1") (pintype "passive"))
      (node (ref "IC1") (pin "5") (pinfunction "IN+_5") (pintype "input"))
      (node (ref "R16") (pin "2") (pinfunction "2_2") (pintype "bidirectional"))
      (node (ref "R18") (pin "2") (pinfunction "2_2") (pintype "bidirectional"))
    )
    (net (code "43") (name "Net-(IC1B-IN-)") (class "Default")
      (node (ref "C30") (pin "1") (pinfunction "1_1") (pintype "bidirectional"))
      (node (ref "IC1") (pin "6") (pinfunction "IN-_6") (pintype "input"))
      (node (ref "R19") (pin "1") (pinfunction "1_1") (pintype "bidirectional"))
      (node (ref "R27") (pin "2") (pinfunction "2_2") (pintype "bidirectional"))
      (node (ref "R28") (pin "2") (pinfunction "2_2") (pintype "bidirectional"))
    )
    (net (code "44") (name "Net-(IC1B-OUT)") (class "Default")
      (node (ref "C30") (pin "2") (pinfunction "2_2") (pintype "bidirectional"))
      (node (ref "IC1") (pin "7") (pinfunction "OUT_7") (pintype "output"))
      (node (ref "R19") (pin "2") (pinfunction "2_2") (pintype "bidirectional"))
      (node (ref "U$2") (pin "6") (pinfunction "6_6") (pintype "bidirectional"))
    )
    (net (code "45") (name "Net-(IC2A-IN+)") (class "Default")
      (node (ref "IC2") (pin "3") (pinfunction "IN+_3") (pintype "input"))
      (node (ref "IC2") (pin "5") (pinfunction "IN+_5") (pintype "input"))
      (node (ref "R25") (pin "2") (pinfunction "2_2") (pintype "bidirectional"))
      (node (ref "U$3") (pin "2") (pinfunction "2_2") (pintype "passive"))
    )
    (net (code "46") (name "Net-(IC2A-IN-)") (class "Default")
      (node (ref "IC2") (pin "1") (pinfunction "OUT_1") (pintype "output"))
      (node (ref "IC2") (pin "2") (pinfunction "IN-_2") (pintype "input"))
      (node (ref "R21") (pin "1") (pinfunction "1_1") (pintype "bidirectional"))
    )
    (net (code "47") (name "Net-(IC2B-IN-)") (class "Default")
      (node (ref "IC2") (pin "6") (pinfunction "IN-_6") (pintype "input"))
      (node (ref "IC2") (pin "7") (pinfunction "OUT_7") (pintype "output"))
      (node (ref "R22") (pin "1") (pinfunction "1_1") (pintype "bidirectional"))
    )
    (net (code "48") (name "Net-(IC3A-IN+)") (class "Default")
      (node (ref "IC3") (pin "3") (pinfunction "IN+_3") (pintype "input"))
      (node (ref "IC3") (pin "5") (pinfunction "IN+_5") (pintype "input"))
      (node (ref "R26") (pin "2") (pinfunction "2_2") (pintype "bidirectional"))
      (node (ref "U$4") (pin "1") (pinfunction "1_1") (pintype "passive"))
    )
    (net (code "49") (name "Net-(IC3A-IN-)") (class "Default")
      (node (ref "IC3") (pin "1") (pinfunction "OUT_1") (pintype "output"))
      (node (ref "IC3") (pin "2") (pinfunction "IN-_2") (pintype "input"))
      (node (ref "R23") (pin "1") (pinfunction "1_1") (pintype "bidirectional"))
    )
    (net (code "50") (name "Net-(IC3B-IN-)") (class "Default")
      (node (ref "IC3") (pin "6") (pinfunction "IN-_6") (pintype "input"))
      (node (ref "IC3") (pin "7") (pinfunction "OUT_7") (pintype "output"))
      (node (ref "R24") (pin "1") (pinfunction "1_1") (pintype "bidirectional"))
    )
    (net (code "51") (name "Net-(JP1-Pad1)") (class "Default")
      (node (ref "JP1") (pin "1") (pinfunction "1_1") (pintype "passive"))
      (node (ref "X1") (pin "2") (pinfunction "2_2") (pintype "passive"))
    )
    (net (code "52") (name "Net-(JP1-Pad2)") (class "Default")
      (node (ref "JP1") (pin "2") (pinfunction "2_2") (pintype "passive"))
      (node (ref "X1") (pin "5") (pinfunction "5_5") (pintype "passive"))
    )
    (net (code "53") (name "Net-(JP1-Pad3)") (class "Default")
      (node (ref "JP1") (pin "3") (pinfunction "3_3") (pintype "passive"))
      (node (ref "R16") (pin "1") (pinfunction "1_1") (pintype "bidirectional"))
    )
    (net (code "54") (name "Net-(JP1-Pad4)") (class "Default")
      (node (ref "JP1") (pin "4") (pinfunction "4_4") (pintype "passive"))
      (node (ref "R15") (pin "1") (pinfunction "1_1") (pintype "bidirectional"))
    )
    (net (code "55") (name "Net-(JP2-Pad1)") (class "Default")
      (node (ref "JP2") (pin "1") (pinfunction "1_1") (pintype "passive"))
      (node (ref "R27") (pin "1") (pinfunction "1_1") (pintype "bidirectional"))
    )
    (net (code "56") (name "Net-(JP2-Pad2)") (class "Default")
      (node (ref "JP2") (pin "2") (pinfunction "2_2") (pintype "passive"))
      (node (ref "R30") (pin "1") (pinfunction "1_1") (pintype "bidirectional"))
    )
    (net (code "57") (name "Net-(JP2-Pad5)") (class "Default")
      (node (ref "JP2") (pin "5") (pinfunction "5_5") (pintype "passive"))
      (node (ref "R28") (pin "1") (pinfunction "1_1") (pintype "bidirectional"))
    )
    (net (code "58") (name "Net-(JP2-Pad6)") (class "Default")
      (node (ref "JP2") (pin "6") (pinfunction "6_6") (pintype "passive"))
      (node (ref "R29") (pin "1") (pinfunction "1_1") (pintype "bidirectional"))
    )
    (net (code "59") (name "Net-(OA5A-IN+)") (class "Default")
      (node (ref "C12") (pin "1") (pinfunction "1_1") (pintype "bidirectional"))
      (node (ref "OA5") (pin "3") (pinfunction "IN+_3") (pintype "bidirectional"))
      (node (ref "R10") (pin "2") (pinfunction "2_2") (pintype "bidirectional"))
      (node (ref "R6") (pin "2") (pinfunction "2_2") (pintype "bidirectional"))
    )
    (net (code "60") (name "Net-(OA5A-IN-)") (class "Default")
      (node (ref "C9") (pin "2") (pinfunction "2_2") (pintype "bidirectional"))
      (node (ref "OA5") (pin "2") (pinfunction "IN-_2") (pintype "bidirectional"))
      (node (ref "R5") (pin "2") (pinfunction "2_2") (pintype "bidirectional"))
      (node (ref "R9") (pin "1") (pinfunction "1_1") (pintype "bidirectional"))
    )
    (net (code "61") (name "Net-(OA6A-IN+)") (class "Default")
      (node (ref "C11") (pin "1") (pinfunction "1_1") (pintype "bidirectional"))
      (node (ref "OA6") (pin "3") (pinfunction "IN+_3") (pintype "bidirectional"))
      (node (ref "R12") (pin "2") (pinfunction "2_2") (pintype "bidirectional"))
      (node (ref "R8") (pin "2") (pinfunction "2_2") (pintype "bidirectional"))
    )
    (net (code "62") (name "Net-(OA6A-IN-)") (class "Default")
      (node (ref "C10") (pin "2") (pinfunction "2_2") (pintype "bidirectional"))
      (node (ref "OA6") (pin "2") (pinfunction "IN-_2") (pintype "bidirectional"))
      (node (ref "R11") (pin "1") (pinfunction "1_1") (pintype "bidirectional"))
      (node (ref "R7") (pin "2") (pinfunction "2_2") (pintype "bidirectional"))
    )
    (net (code "63") (name "Net-(R21-Pad2)") (class "Default")
      (node (ref "R21") (pin "2") (pinfunction "2_2") (pintype "bidirectional"))
      (node (ref "R22") (pin "2") (pinfunction "2_2") (pintype "bidirectional"))
      (node (ref "X2") (pin "2") (pinfunction "2_2") (pintype "passive"))
    )
    (net (code "64") (name "Net-(R23-Pad2)") (class "Default")
      (node (ref "R23") (pin "2") (pinfunction "2_2") (pintype "bidirectional"))
      (node (ref "R24") (pin "2") (pinfunction "2_2") (pintype "bidirectional"))
      (node (ref "X2") (pin "5") (pinfunction "5_5") (pintype "passive"))
    )
    (net (code "65") (name "Net-(U$2-Pad2)") (class "Default")
      (node (ref "U$2") (pin "2") (pinfunction "2_2") (pintype "bidirectional"))
      (node (ref "U$4") (pin "2") (pinfunction "2_2") (pintype "passive"))
    )
    (net (code "66") (name "Net-(U$2-Pad5)") (class "Default")
      (node (ref "U$2") (pin "5") (pinfunction "5_5") (pintype "bidirectional"))
      (node (ref "U$3") (pin "1") (pinfunction "1_1") (pintype "passive"))
    )
    (net (code "67") (name "Net-(U1-VCC1)") (class "Default")
      (node (ref "C65") (pin "+") (pinfunction "+_+") (pintype "passive"))
      (node (ref "C66") (pin "+") (pinfunction "+_+") (pintype "passive"))
      (node (ref "C69") (pin "+") (pinfunction "+_+") (pintype "passive"))
      (node (ref "U1") (pin "23") (pinfunction "VCC1_23") (pintype "power_in"))
    )
    (net (code "68") (name "Net-(U1-VCC2L)") (class "Default")
      (node (ref "C67") (pin "+") (pinfunction "+_+") (pintype "passive"))
      (node (ref "C71") (pin "1") (pinfunction "1_1") (pintype "passive"))
      (node (ref "U1") (pin "28") (pinfunction "VCC2L_28") (pintype "power_in"))
    )
    (net (code "69") (name "Net-(U1-VCC2R)") (class "Default")
      (node (ref "C68") (pin "+") (pinfunction "+_+") (pintype "passive"))
      (node (ref "C72") (pin "1") (pinfunction "1_1") (pintype "passive"))
      (node (ref "U1") (pin "15") (pinfunction "VCC2R_15") (pintype "power_in"))
    )
    (net (code "70") (name "Net-(U1-VCOML)") (class "Default")
      (node (ref "C65") (pin "-") (pinfunction "-_-") (pintype "passive"))
      (node (ref "U1") (pin "22") (pinfunction "VCOML_22") (pintype "input"))
    )
    (net (code "71") (name "Net-(U1-VCOMR)") (class "Default")
      (node (ref "C66") (pin "-") (pinfunction "-_-") (pintype "passive"))
      (node (ref "U1") (pin "21") (pinfunction "VCOMR_21") (pintype "input"))
    )
    (net (code "72") (name "Net-(U1-VDD)") (class "Default")
      (node (ref "C70") (pin "+") (pinfunction "+_+") (pintype "passive"))
      (node (ref "C73") (pin "1") (pinfunction "1_1") (pintype "passive"))
      (node (ref "U1") (pin "9") (pinfunction "VDD_9") (pintype "power_in"))
    )
    (net (code "73") (name "RST#") (class "Default")
      (node (ref "U1") (pin "14") (pinfunction "~{RST}_14") (pintype "input"))
    )
    (net (code "74") (name "SCK") (class "Default")
      (node (ref "U$1") (pin "18") (pinfunction "FUNC2_18") (pintype "bidirectional"))
      (node (ref "U1") (pin "7") (pinfunction "SCK_7") (pintype "input"))
    )
    (net (code "75") (name "USB_D+") (class "Default")
      (node (ref "R36") (pin "P$2") (pinfunction "2_P$2") (pintype "bidirectional"))
      (node (ref "U$9") (pin "D+") (pinfunction "D+_D+") (pintype "bidirectional"))
    )
    (net (code "76") (name "USB_D-") (class "Default")
      (node (ref "R37") (pin "P$2") (pinfunction "2_P$2") (pintype "bidirectional"))
      (node (ref "U$9") (pin "D-") (pinfunction "D-_D-") (pintype "bidirectional"))
    )
    (net (code "77") (name "USB_VBUS") (class "Default")
      (node (ref "L1") (pin "2") (pinfunction "2_2") (pintype "passive"))
      (node (ref "U$9") (pin "VBUS") (pinfunction "VBUS_VBUS") (pintype "bidirectional"))
    )
    (net (code "78") (name "V+") (class "Default")
      (node (ref "C16") (pin "P$1") (pinfunction "1_P$1") (pintype "bidirectional"))
      (node (ref "C17") (pin "P$1") (pinfunction "1_P$1") (pintype "bidirectional"))
      (node (ref "C19") (pin "P$1") (pinfunction "1_P$1") (pintype "bidirectional"))
      (node (ref "C21") (pin "P$1") (pinfunction "1_P$1") (pintype "bidirectional"))
      (node (ref "C23") (pin "P$1") (pinfunction "1_P$1") (pintype "bidirectional"))
      (node (ref "C25") (pin "P$1") (pinfunction "1_P$1") (pintype "bidirectional"))
      (node (ref "IC1") (pin "8") (pinfunction "V+_8") (pintype "power_in"))
      (node (ref "IC2") (pin "8") (pinfunction "V+_8") (pintype "power_in"))
      (node (ref "IC3") (pin "8") (pinfunction "V+_8") (pintype "power_in"))
      (node (ref "OA1") (pin "7") (pinfunction "V+_7") (pintype "power_in"))
      (node (ref "OA2") (pin "7") (pinfunction "V+_7") (pintype "power_in"))
      (node (ref "OA3") (pin "7") (pinfunction "V+_7") (pintype "power_in"))
      (node (ref "OA4") (pin "7") (pinfunction "V+_7") (pintype "power_in"))
      (node (ref "OA5") (pin "7") (pinfunction "V+_7") (pintype "power_in"))
      (node (ref "OA6") (pin "7") (pinfunction "V+_7") (pintype "power_in"))
    )
    (net (code "79") (name "V-") (class "Default")
      (node (ref "C15") (pin "P$1") (pinfunction "1_P$1") (pintype "bidirectional"))
      (node (ref "C18") (pin "P$1") (pinfunction "1_P$1") (pintype "bidirectional"))
      (node (ref "C20") (pin "P$1") (pinfunction "1_P$1") (pintype "bidirectional"))
      (node (ref "C22") (pin "P$1") (pinfunction "1_P$1") (pintype "bidirectional"))
      (node (ref "C24") (pin "P$1") (pinfunction "1_P$1") (pintype "bidirectional"))
      (node (ref "C26") (pin "P$1") (pinfunction "1_P$1") (pintype "bidirectional"))
      (node (ref "IC1") (pin "4") (pinfunction "V-_4") (pintype "power_in"))
      (node (ref "IC2") (pin "4") (pinfunction "V-_4") (pintype "power_in"))
      (node (ref "IC3") (pin "4") (pinfunction "V-_4") (pintype "power_in"))
      (node (ref "OA1") (pin "4") (pinfunction "V-_4") (pintype "power_in"))
      (node (ref "OA2") (pin "4") (pinfunction "V-_4") (pintype "power_in"))
      (node (ref "OA3") (pin "4") (pinfunction "V-_4") (pintype "power_in"))
      (node (ref "OA4") (pin "4") (pinfunction "V-_4") (pintype "power_in"))
      (node (ref "OA5") (pin "4") (pinfunction "V-_4") (pintype "power_in"))
      (node (ref "OA6") (pin "4") (pinfunction "V-_4") (pintype "power_in"))
    )
    (net (code "80") (name "VBUS") (class "Default")
      (node (ref "L1") (pin "1") (pinfunction "1_1") (pintype "passive"))
      (node (ref "U$1") (pin "24") (pinfunction "VBUS_24") (pintype "bidirectional"))
    )
    (net (code "81") (name "VCCL") (class "Default")
      (node (ref "C61") (pin "P$1") (pinfunction "1_P$1") (pintype "bidirectional"))
      (node (ref "U$1") (pin "27") (pinfunction "VCCL_27") (pintype "bidirectional"))
    )
    (net (code "82") (name "VCCP") (class "Default")
      (node (ref "C58") (pin "P$2") (pinfunction "2_P$2") (pintype "bidirectional"))
      (node (ref "U$1") (pin "2") (pinfunction "VCCP_2") (pintype "bidirectional"))
    )
    (net (code "83") (name "VCCR") (class "Default")
      (node (ref "C60") (pin "P$2") (pinfunction "2_P$2") (pintype "bidirectional"))
      (node (ref "U$1") (pin "30") (pinfunction "VCCR_30") (pintype "bidirectional"))
    )
    (net (code "84") (name "VCOM") (class "Default")
      (node (ref "C59") (pin "+") (pinfunction "+_+") (pintype "passive"))
      (node (ref "U$1") (pin "32") (pinfunction "VCOM_32") (pintype "bidirectional"))
    )
    (net (code "85") (name "VDD") (class "Default")
      (node (ref "C64") (pin "P$1") (pinfunction "1_P$1") (pintype "bidirectional"))
      (node (ref "U$1") (pin "21") (pinfunction "VDD_21") (pintype "bidirectional"))
    )
    (net (code "86") (name "unconnected-(OA1A-BAL-Pad1)") (class "Default")
      (node (ref "OA1") (pin "1") (pinfunction "BAL_1") (pintype "bidirectional"))
    )
    (net (code "87") (name "unconnected-(OA2A-BAL-Pad1)") (class "Default")
      (node (ref "OA2") (pin "1") (pinfunction "BAL_1") (pintype "bidirectional"))
    )
    (net (code "88") (name "unconnected-(OA3A-BAL-Pad1)") (class "Default")
      (node (ref "OA3") (pin "1") (pinfunction "BAL_1") (pintype "bidirectional"))
    )
    (net (code "89") (name "unconnected-(OA4A-BAL-Pad1)") (class "Default")
      (node (ref "OA4") (pin "1") (pinfunction "BAL_1") (pintype "bidirectional"))
    )
    (net (code "90") (name "unconnected-(OA5A-BAL-Pad1)") (class "Default")
      (node (ref "OA5") (pin "1") (pinfunction "BAL_1") (pintype "bidirectional"))
    )
    (net (code "91") (name "unconnected-(OA5A-COMP{slash}BAL-Pad8)") (class "Default")
      (node (ref "OA5") (pin "8") (pinfunction "COMP/BAL_8") (pintype "bidirectional"))
    )
    (net (code "92") (name "unconnected-(OA6A-BAL-Pad1)") (class "Default")
      (node (ref "OA6") (pin "1") (pinfunction "BAL_1") (pintype "bidirectional"))
    )
    (net (code "93") (name "unconnected-(OA6A-COMP{slash}BAL-Pad8)") (class "Default")
      (node (ref "OA6") (pin "8") (pinfunction "COMP/BAL_8") (pintype "bidirectional"))
    )
    (net (code "94") (name "unconnected-(R13-Pad2)") (class "Default")
      (node (ref "R13") (pin "2") (pinfunction "2_2") (pintype "bidirectional"))
    )
    (net (code "95") (name "unconnected-(R14-Pad2)") (class "Default")
      (node (ref "R14") (pin "2") (pinfunction "2_2") (pintype "bidirectional"))
    )
    (net (code "96") (name "unconnected-(U$1-CK-Pad14)") (class "Default")
      (node (ref "U$1") (pin "14") (pinfunction "CK_14") (pintype "bidirectional"))
    )
    (net (code "97") (name "unconnected-(U$1-DT-Pad15)") (class "Default")
      (node (ref "U$1") (pin "15") (pinfunction "DT_15") (pintype "bidirectional"))
    )
    (net (code "98") (name "unconnected-(U$1-FSEL-Pad9)") (class "Default")
      (node (ref "U$1") (pin "9") (pinfunction "FSEL_9") (pintype "bidirectional"))
    )
    (net (code "99") (name "unconnected-(U$1-FUNC3-Pad4)") (class "Default")
      (node (ref "U$1") (pin "4") (pinfunction "FUNC3_4") (pintype "bidirectional"))
    )
    (net (code "100") (name "unconnected-(U$1-HID1{slash}MC-Pad7)") (class "Default")
      (node (ref "U$1") (pin "7") (pinfunction "HID1/MC_7") (pintype "bidirectional"))
    )
    (net (code "101") (name "unconnected-(U$1-HID2{slash}MD-Pad8)") (class "Default")
      (node (ref "U$1") (pin "8") (pinfunction "HID2/MD_8") (pintype "bidirectional"))
    )
    (net (code "102") (name "unconnected-(U$1-HIDO{slash}MS-Pad6)") (class "Default")
      (node (ref "U$1") (pin "6") (pinfunction "HIDO/MS_6") (pintype "bidirectional"))
    )
    (net (code "103") (name "unconnected-(U$1-HOST-Pad3)") (class "Default")
      (node (ref "U$1") (pin "3") (pinfunction "HOST_3") (pintype "bidirectional"))
    )
    (net (code "104") (name "unconnected-(U$1-PSEL-Pad16)") (class "Default")
      (node (ref "U$1") (pin "16") (pinfunction "PSEL_16") (pintype "bidirectional"))
    )
    (net (code "105") (name "unconnected-(U$1-SSPND\\-Pad11)") (class "Default")
      (node (ref "U$1") (pin "11") (pinfunction "SSPND\\_11") (pintype "bidirectional"))
    )
    (net (code "106") (name "unconnected-(U$1-TEST-Pad10)") (class "Default")
      (node (ref "U$1") (pin "10") (pinfunction "TEST_10") (pintype "bidirectional"))
    )
    (net (code "107") (name "unconnected-(U$1-VOUTL-Pad28)") (class "Default")
      (node (ref "U$1") (pin "28") (pinfunction "VOUTL_28") (pintype "bidirectional"))
    )
    (net (code "108") (name "unconnected-(U$1-VOUTR-Pad29)") (class "Default")
      (node (ref "U$1") (pin "29") (pinfunction "VOUTR_29") (pintype "bidirectional"))
    )
    (net (code "109") (name "unconnected-(U$9-PadID)") (class "Default")
      (node (ref "U$9") (pin "ID") (pinfunction "ID_ID") (pintype "bidirectional"))
    )
    (net (code "110") (name "unconnected-(U1-IREF-Pad20)") (class "Default")
      (node (ref "U1") (pin "20") (pinfunction "IREF_20") (pintype "output"))
    )
    (net (code "111") (name "unconnected-(U1-ZERO-Pad13)") (class "Default")
      (node (ref "U1") (pin "13") (pinfunction "ZERO_13") (pintype "output"))
    )
    (net (code "112") (name "unconnected-(X2-Pad3)") (class "Default")
      (node (ref "X2") (pin "3") (pinfunction "3_3") (pintype "passive"))
    )
    (net (code "113") (name "unconnected-(X2-Pad4)") (class "Default")
      (node (ref "X2") (pin "4") (pinfunction "4_4") (pintype "passive"))
    )
  )
)
